# RH005_1.net
KiCad netlist of a schematic drawn in EAGLE
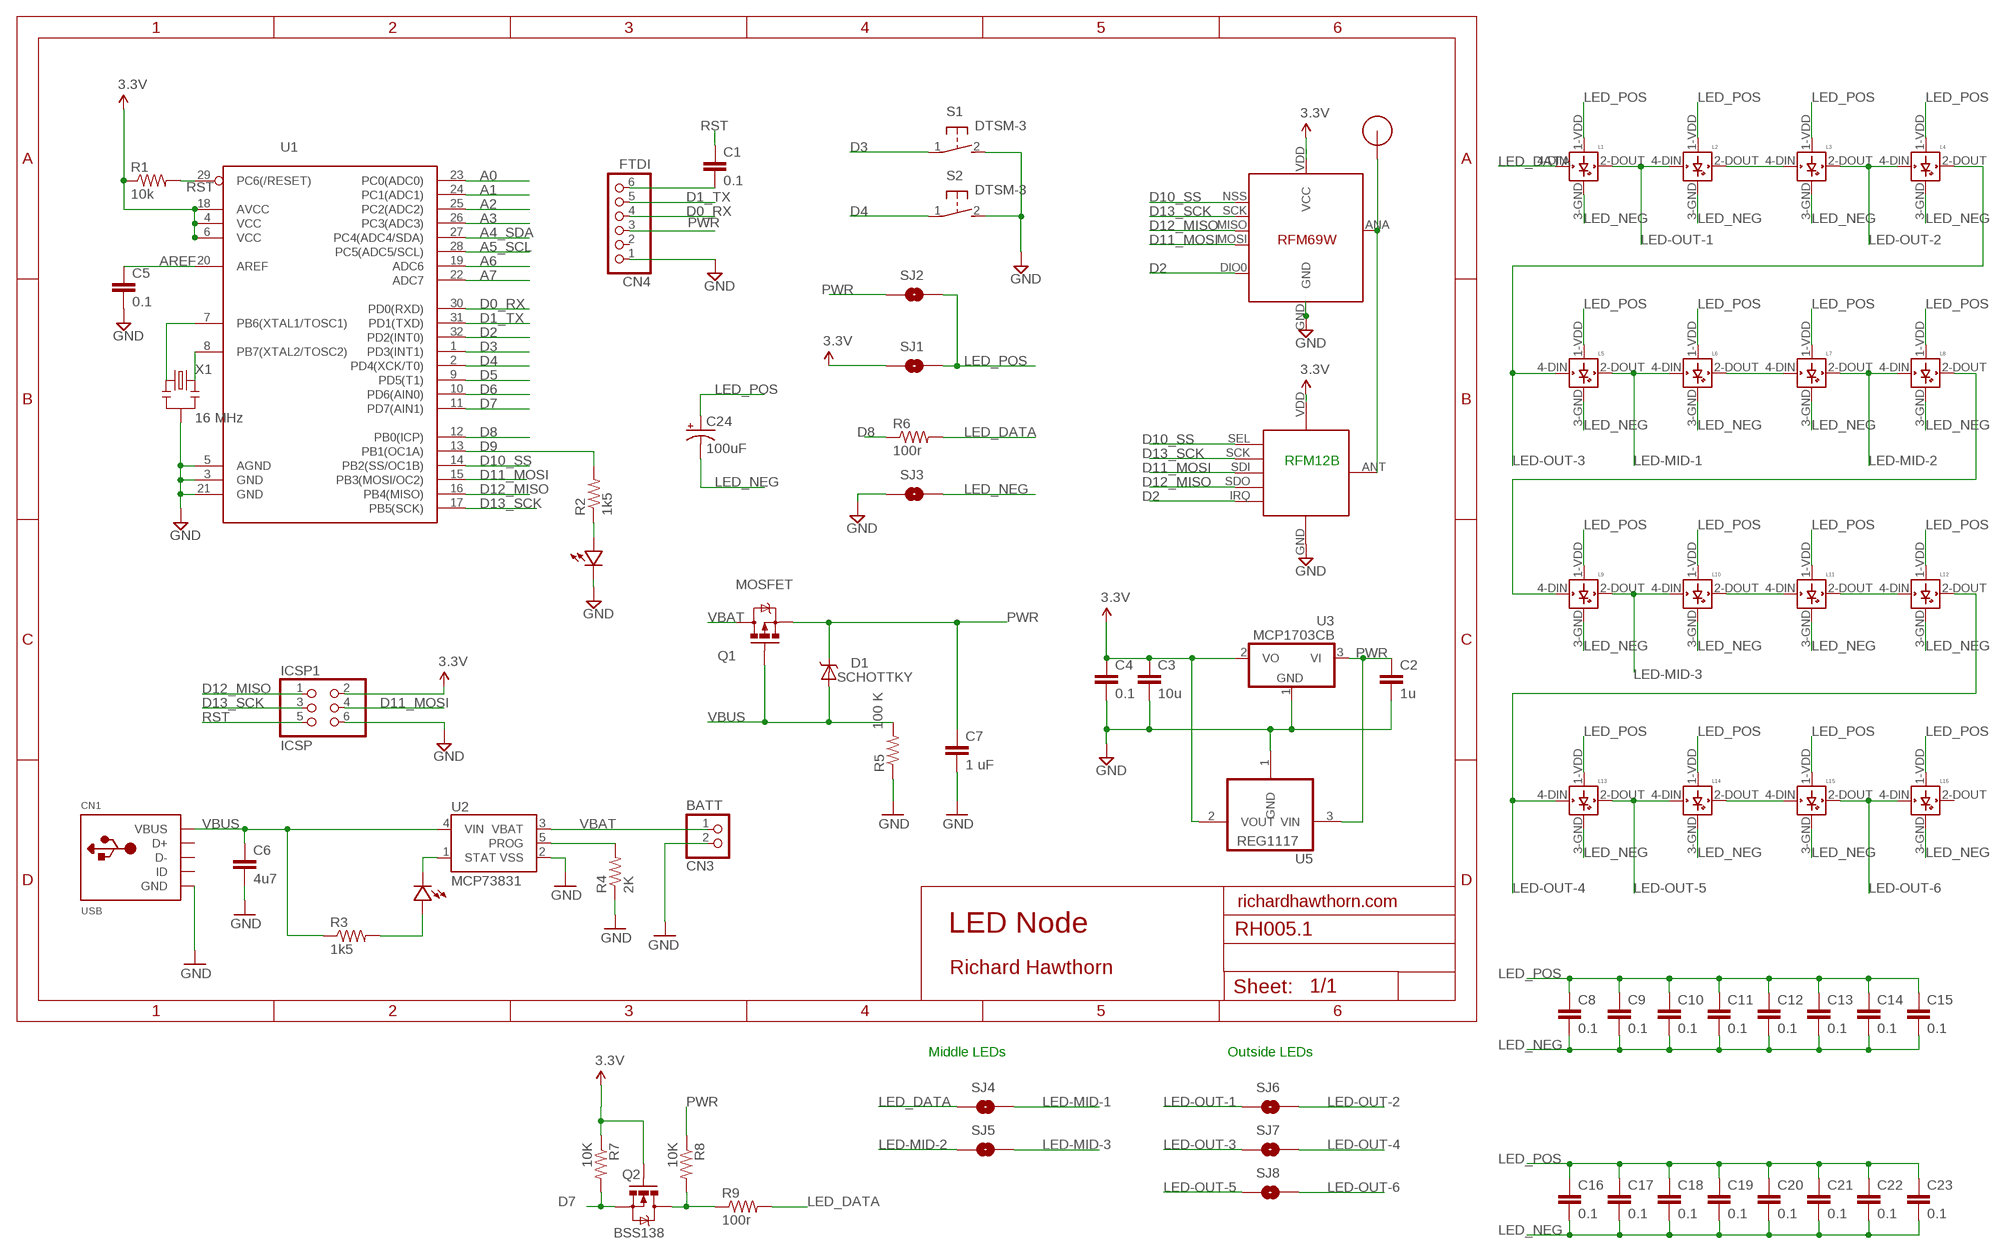
[diagram p0: schematic, sheet 1]

(export (version "E")
  (design (tool "Eeschema 10.0.6"))
  (components
    (comp (ref "C1")
      (value "0.1")
      (footprint "eagle-import:0603-CAP")
      (libsource (lib "eagle-import") (part "CAP0603-CAP"))
    )
    (comp (ref "C2")
      (value "1u")
      (footprint "eagle-import:0603-CAP")
      (libsource (lib "eagle-import") (part "CAP0603-CAP"))
    )
    (comp (ref "C3")
      (value "10u")
      (footprint "eagle-import:0805-CAP")
      (libsource (lib "eagle-import") (part "CAP0805-CAP"))
    )
    (comp (ref "C4")
      (value "0.1")
      (footprint "eagle-import:0603-CAP")
      (libsource (lib "eagle-import") (part "CAP0603-CAP"))
    )
    (comp (ref "C5")
      (value "0.1")
      (footprint "eagle-import:0603-CAP")
      (libsource (lib "eagle-import") (part "CAP0603-CAP"))
    )
    (comp (ref "C6")
      (value "4u7")
      (footprint "eagle-import:0603-CAP")
      (libsource (lib "eagle-import") (part "SparkFun_CAP0603-CAP"))
    )
    (comp (ref "C7")
      (value "1 uF")
      (footprint "eagle-import:0805")
      (libsource (lib "eagle-import") (part "SparkFun-Capacitors_CAP0805"))
    )
    (comp (ref "C8")
      (value "0.1")
      (footprint "eagle-import:0603-CAP")
      (libsource (lib "eagle-import") (part "CAP0603-CAP"))
    )
    (comp (ref "C9")
      (value "0.1")
      (footprint "eagle-import:0603-CAP")
      (libsource (lib "eagle-import") (part "CAP0603-CAP"))
    )
    (comp (ref "C10")
      (value "0.1")
      (footprint "eagle-import:0603-CAP")
      (libsource (lib "eagle-import") (part "CAP0603-CAP"))
    )
    (comp (ref "C11")
      (value "0.1")
      (footprint "eagle-import:0603-CAP")
      (libsource (lib "eagle-import") (part "CAP0603-CAP"))
    )
    (comp (ref "C12")
      (value "0.1")
      (footprint "eagle-import:0603-CAP")
      (libsource (lib "eagle-import") (part "CAP0603-CAP"))
    )
    (comp (ref "C13")
      (value "0.1")
      (footprint "eagle-import:0603-CAP")
      (libsource (lib "eagle-import") (part "CAP0603-CAP"))
    )
    (comp (ref "C14")
      (value "0.1")
      (footprint "eagle-import:0603-CAP")
      (libsource (lib "eagle-import") (part "CAP0603-CAP"))
    )
    (comp (ref "C15")
      (value "0.1")
      (footprint "eagle-import:0603-CAP")
      (libsource (lib "eagle-import") (part "CAP0603-CAP"))
    )
    (comp (ref "C16")
      (value "0.1")
      (footprint "eagle-import:0603-CAP")
      (libsource (lib "eagle-import") (part "CAP0603-CAP"))
    )
    (comp (ref "C17")
      (value "0.1")
      (footprint "eagle-import:0603-CAP")
      (libsource (lib "eagle-import") (part "CAP0603-CAP"))
    )
    (comp (ref "C18")
      (value "0.1")
      (footprint "eagle-import:0603-CAP")
      (libsource (lib "eagle-import") (part "CAP0603-CAP"))
    )
    (comp (ref "C19")
      (value "0.1")
      (footprint "eagle-import:0603-CAP")
      (libsource (lib "eagle-import") (part "CAP0603-CAP"))
    )
    (comp (ref "C20")
      (value "0.1")
      (footprint "eagle-import:0603-CAP")
      (libsource (lib "eagle-import") (part "CAP0603-CAP"))
    )
    (comp (ref "C21")
      (value "0.1")
      (footprint "eagle-import:0603-CAP")
      (libsource (lib "eagle-import") (part "CAP0603-CAP"))
    )
    (comp (ref "C22")
      (value "0.1")
      (footprint "eagle-import:0603-CAP")
      (libsource (lib "eagle-import") (part "CAP0603-CAP"))
    )
    (comp (ref "C23")
      (value "0.1")
      (footprint "eagle-import:0603-CAP")
      (libsource (lib "eagle-import") (part "CAP0603-CAP"))
    )
    (comp (ref "C24")
      (value "100uF")
      (footprint "eagle-import:EIA7343")
      (libsource (lib "eagle-import") (part "100UF-10V-10%(TANT)"))
    )
    (comp (ref "CN1")
      (value "USB")
      (footprint "eagle-import:USB-MINIB")
      (libsource (lib "eagle-import") (part "USBMINIB"))
    )
    (comp (ref "CN3")
      (value "BATT")
      (footprint "eagle-import:JST-PH-2-SMT-RA")
      (libsource (lib "eagle-import") (part "JST_2PIN-SMT-RA"))
    )
    (comp (ref "CN4")
      (value "FTDI")
      (footprint "eagle-import:1X06")
      (libsource (lib "eagle-import") (part "PINHD-1X6"))
    )
    (comp (ref "D1")
      (value "SCHOTTKY")
      (footprint "eagle-import:SMA-DIODE")
      (libsource (lib "eagle-import") (part "DIODE-SCHOTTKY_"))
    )
    (comp (ref "ICSP1")
      (value "ICSP")
      (footprint "eagle-import:2X03")
      (libsource (lib "eagle-import") (part "PINHD-2X3"))
    )
    (comp (ref "L1")
      (value "WS2812B")
      (footprint "eagle-import:WS2812B")
      (libsource (lib "eagle-import") (part "WS2812B"))
    )
    (comp (ref "L2")
      (value "WS2812B")
      (footprint "eagle-import:WS2812B")
      (libsource (lib "eagle-import") (part "WS2812B"))
    )
    (comp (ref "L3")
      (value "WS2812B")
      (footprint "eagle-import:WS2812B")
      (libsource (lib "eagle-import") (part "WS2812B"))
    )
    (comp (ref "L4")
      (value "WS2812B")
      (footprint "eagle-import:WS2812B")
      (libsource (lib "eagle-import") (part "WS2812B"))
    )
    (comp (ref "L5")
      (value "WS2812B")
      (footprint "eagle-import:WS2812B")
      (libsource (lib "eagle-import") (part "WS2812B"))
    )
    (comp (ref "L6")
      (value "WS2812B")
      (footprint "eagle-import:WS2812B")
      (libsource (lib "eagle-import") (part "WS2812B"))
    )
    (comp (ref "L7")
      (value "WS2812B")
      (footprint "eagle-import:WS2812B")
      (libsource (lib "eagle-import") (part "WS2812B"))
    )
    (comp (ref "L8")
      (value "WS2812B")
      (footprint "eagle-import:WS2812B")
      (libsource (lib "eagle-import") (part "WS2812B"))
    )
    (comp (ref "L9")
      (value "WS2812B")
      (footprint "eagle-import:WS2812B")
      (libsource (lib "eagle-import") (part "WS2812B"))
    )
    (comp (ref "L10")
      (value "WS2812B")
      (footprint "eagle-import:WS2812B")
      (libsource (lib "eagle-import") (part "WS2812B"))
    )
    (comp (ref "L11")
      (value "WS2812B")
      (footprint "eagle-import:WS2812B")
      (libsource (lib "eagle-import") (part "WS2812B"))
    )
    (comp (ref "L12")
      (value "WS2812B")
      (footprint "eagle-import:WS2812B")
      (libsource (lib "eagle-import") (part "WS2812B"))
    )
    (comp (ref "L13")
      (value "WS2812B")
      (footprint "eagle-import:WS2812B")
      (libsource (lib "eagle-import") (part "WS2812B"))
    )
    (comp (ref "L14")
      (value "WS2812B")
      (footprint "eagle-import:WS2812B")
      (libsource (lib "eagle-import") (part "WS2812B"))
    )
    (comp (ref "L15")
      (value "WS2812B")
      (footprint "eagle-import:WS2812B")
      (libsource (lib "eagle-import") (part "WS2812B"))
    )
    (comp (ref "L16")
      (value "WS2812B")
      (footprint "eagle-import:WS2812B")
      (libsource (lib "eagle-import") (part "WS2812B"))
    )
    (comp (ref "LED1")
      (value "LED0603")
      (footprint "eagle-import:0603-LED")
      (libsource (lib "eagle-import") (part "LED0603"))
    )
    (comp (ref "LED2")
      (value "LED0603")
      (footprint "eagle-import:0603-LED")
      (libsource (lib "eagle-import") (part "LED0603"))
    )
    (comp (ref "Q1")
      (value "MOSFET")
      (footprint "eagle-import:SOT23-3")
      (libsource (lib "eagle-import") (part "MOSFET-PCHANNELSMD"))
    )
    (comp (ref "Q2")
      (value "BSS138")
      (footprint "eagle-import:SOT23-3")
      (libsource (lib "eagle-import") (part "MOSFET-NCHANNELSMD"))
    )
    (comp (ref "R1")
      (value "10k")
      (footprint "eagle-import:0603-RES")
      (libsource (lib "eagle-import") (part "RESISTOR0603-RES"))
    )
    (comp (ref "R2")
      (value "1k5")
      (footprint "eagle-import:0603-RES")
      (libsource (lib "eagle-import") (part "RESISTOR0603-RES"))
    )
    (comp (ref "R3")
      (value "1k5")
      (footprint "eagle-import:0603-RES")
      (libsource (lib "eagle-import") (part "RESISTOR0603-RES"))
    )
    (comp (ref "R4")
      (value "2K")
      (footprint "eagle-import:0603-RES")
      (libsource (lib "eagle-import") (part "RESISTOR0603-RES"))
    )
    (comp (ref "R5")
      (value "100 K")
      (footprint "eagle-import:0805")
      (libsource (lib "eagle-import") (part "SparkFun-Resistors_RESISTOR0805-RES"))
    )
    (comp (ref "R6")
      (value "100r")
      (footprint "eagle-import:0603-RES")
      (libsource (lib "eagle-import") (part "RESISTOR0603-RES"))
    )
    (comp (ref "R7")
      (value "10K")
      (footprint "eagle-import:0805")
      (libsource (lib "eagle-import") (part "SparkFun-Passives_RESISTOR0805-RES"))
    )
    (comp (ref "R8")
      (value "10K")
      (footprint "eagle-import:0805")
      (libsource (lib "eagle-import") (part "SparkFun-Passives_RESISTOR0805-RES"))
    )
    (comp (ref "R9")
      (value "100r")
      (footprint "eagle-import:0603-RES")
      (libsource (lib "eagle-import") (part "RESISTOR0603-RES"))
    )
    (comp (ref "RF1")
      (value "RFM12B")
      (footprint "eagle-import:RFM12B-MINPADS")
      (libsource (lib "eagle-import") (part "RFM12B_MINPADS"))
    )
    (comp (ref "RF2")
      (value "RFM69")
      (footprint "eagle-import:RFM69W-MINPADS")
      (libsource (lib "eagle-import") (part "RFM69"))
    )
    (comp (ref "S1")
      (value "DTSM-3")
      (footprint "eagle-import:DTSM-3")
      (libsource (lib "eagle-import") (part "DTSM-3"))
    )
    (comp (ref "S2")
      (value "DTSM-3")
      (footprint "eagle-import:DTSM-3")
      (libsource (lib "eagle-import") (part "DTSM-3"))
    )
    (comp (ref "SJ1")
      (value "SOLDERJUMPERNO")
      (footprint "eagle-import:SJ_2S-NO")
      (libsource (lib "eagle-import") (part "SOLDERJUMPERNO"))
    )
    (comp (ref "SJ2")
      (value "SOLDERJUMPERNO")
      (footprint "eagle-import:SJ_2S-NO")
      (libsource (lib "eagle-import") (part "SOLDERJUMPERNO"))
    )
    (comp (ref "SJ3")
      (value "SOLDERJUMPERNO")
      (footprint "eagle-import:SJ_2S-NO")
      (libsource (lib "eagle-import") (part "SOLDERJUMPERNO"))
    )
    (comp (ref "SJ4")
      (value "JUMPER-PAD-2-NOYES_SILK")
      (footprint "eagle-import:PAD-JUMPER-2-NO_YES_SILK")
      (libsource (lib "eagle-import") (part "JUMPER-PAD-2-NOYES_SILK"))
    )
    (comp (ref "SJ5")
      (value "JUMPER-PAD-2-NOYES_SILK")
      (footprint "eagle-import:PAD-JUMPER-2-NO_YES_SILK")
      (libsource (lib "eagle-import") (part "JUMPER-PAD-2-NOYES_SILK"))
    )
    (comp (ref "SJ6")
      (value "JUMPER-PAD-2-NOYES_SILK")
      (footprint "eagle-import:PAD-JUMPER-2-NO_YES_SILK")
      (libsource (lib "eagle-import") (part "JUMPER-PAD-2-NOYES_SILK"))
    )
    (comp (ref "SJ7")
      (value "JUMPER-PAD-2-NOYES_SILK")
      (footprint "eagle-import:PAD-JUMPER-2-NO_YES_SILK")
      (libsource (lib "eagle-import") (part "JUMPER-PAD-2-NOYES_SILK"))
    )
    (comp (ref "SJ8")
      (value "JUMPER-PAD-2-NOYES_SILK")
      (footprint "eagle-import:PAD-JUMPER-2-NO_YES_SILK")
      (libsource (lib "eagle-import") (part "JUMPER-PAD-2-NOYES_SILK"))
    )
    (comp (ref "U$1")
      (value "RFM12B_ANTENNA")
      (footprint "eagle-import:RFM12B-ANTENNA")
      (libsource (lib "eagle-import") (part "RFM12B_ANTENNA"))
    )
    (comp (ref "U1")
      (value "ATMega-328")
      (footprint "eagle-import:TQFP32-08")
      (libsource (lib "eagle-import") (part "ATMEGA168/328TQFP32"))
    )
    (comp (ref "U2")
      (value "MCP73831")
      (footprint "eagle-import:SOT23-5")
      (libsource (lib "eagle-import") (part "MCP73831"))
    )
    (comp (ref "U3")
      (value "MCP1703CB")
      (footprint "eagle-import:SOT23")
      (libsource (lib "eagle-import") (part "MCP1703CB"))
    )
    (comp (ref "U5")
      (value "REG1117")
      (footprint "eagle-import:SOT223")
      (libsource (lib "eagle-import") (part "REG1117"))
    )
    (comp (ref "X1")
      (value "16 MHz")
      (footprint "eagle-import:RESONATOR-SMD")
      (libsource (lib "eagle-import") (part "RESONATORSMD"))
    )
  )
  (nets
    (net (code "1") (name "/A0") (class "Default")
      (node (ref "U1") (pin "23") (pinfunction "PC0(ADC0)_23") (pintype "bidirectional"))
    )
    (net (code "2") (name "/A1") (class "Default")
      (node (ref "U1") (pin "24") (pinfunction "PC1(ADC1)_24") (pintype "bidirectional"))
    )
    (net (code "3") (name "/A2") (class "Default")
      (node (ref "U1") (pin "25") (pinfunction "PC2(ADC2)_25") (pintype "bidirectional"))
    )
    (net (code "4") (name "/A3") (class "Default")
      (node (ref "U1") (pin "26") (pinfunction "PC3(ADC3)_26") (pintype "bidirectional"))
    )
    (net (code "5") (name "/A4_SDA") (class "Default")
      (node (ref "U1") (pin "27") (pinfunction "PC4(ADC4/SDA)_27") (pintype "bidirectional"))
    )
    (net (code "6") (name "/A5_SCL") (class "Default")
      (node (ref "U1") (pin "28") (pinfunction "PC5(ADC5/SCL)_28") (pintype "bidirectional"))
    )
    (net (code "7") (name "/A6") (class "Default")
      (node (ref "U1") (pin "19") (pinfunction "ADC6_19") (pintype "bidirectional"))
    )
    (net (code "8") (name "/A7") (class "Default")
      (node (ref "U1") (pin "22") (pinfunction "ADC7_22") (pintype "bidirectional"))
    )
    (net (code "9") (name "/AREF") (class "Default")
      (node (ref "C5") (pin "1") (pinfunction "1_1") (pintype "passive"))
      (node (ref "U1") (pin "20") (pinfunction "AREF_20") (pintype "bidirectional"))
    )
    (net (code "10") (name "/D0_RX") (class "Default")
      (node (ref "CN4") (pin "4") (pinfunction "4_4") (pintype "passive"))
      (node (ref "U1") (pin "30") (pinfunction "PD0(RXD)_30") (pintype "bidirectional"))
    )
    (net (code "11") (name "/D1_TX") (class "Default")
      (node (ref "CN4") (pin "5") (pinfunction "5_5") (pintype "passive"))
      (node (ref "U1") (pin "31") (pinfunction "PD1(TXD)_31") (pintype "bidirectional"))
    )
    (net (code "12") (name "/D2") (class "Default")
      (node (ref "RF1") (pin "IRQ") (pinfunction "IRQ_IRQ") (pintype "bidirectional"))
      (node (ref "RF2") (pin "DIO0") (pinfunction "DIO0_DIO0") (pintype "open_collector"))
      (node (ref "U1") (pin "32") (pinfunction "PD2(INT0)_32") (pintype "bidirectional"))
    )
    (net (code "13") (name "/D3") (class "Default")
      (node (ref "S1") (pin "1") (pinfunction "1_1") (pintype "passive"))
      (node (ref "U1") (pin "1") (pinfunction "PD3(INT1)_1") (pintype "bidirectional"))
    )
    (net (code "14") (name "/D4") (class "Default")
      (node (ref "S2") (pin "1") (pinfunction "1_1") (pintype "passive"))
      (node (ref "U1") (pin "2") (pinfunction "PD4(XCK/T0)_2") (pintype "bidirectional"))
    )
    (net (code "15") (name "/D5") (class "Default")
      (node (ref "U1") (pin "9") (pinfunction "PD5(T1)_9") (pintype "bidirectional"))
    )
    (net (code "16") (name "/D6") (class "Default")
      (node (ref "U1") (pin "10") (pinfunction "PD6(AIN0)_10") (pintype "bidirectional"))
    )
    (net (code "17") (name "/D7") (class "Default")
      (node (ref "Q2") (pin "2") (pinfunction "S_2") (pintype "passive"))
      (node (ref "R7") (pin "2") (pinfunction "2_2") (pintype "passive"))
      (node (ref "U1") (pin "11") (pinfunction "PD7(AIN1)_11") (pintype "bidirectional"))
    )
    (net (code "18") (name "/D8") (class "Default")
      (node (ref "R6") (pin "1") (pinfunction "1_1") (pintype "passive"))
      (node (ref "U1") (pin "12") (pinfunction "PB0(ICP)_12") (pintype "bidirectional"))
    )
    (net (code "19") (name "/D9") (class "Default")
      (node (ref "R2") (pin "2") (pinfunction "2_2") (pintype "passive"))
      (node (ref "U1") (pin "13") (pinfunction "PB1(OC1A)_13") (pintype "bidirectional"))
    )
    (net (code "20") (name "/D10_SS") (class "Default")
      (node (ref "RF1") (pin "SEL") (pinfunction "SEL_SEL") (pintype "bidirectional"))
      (node (ref "RF2") (pin "NSS") (pinfunction "SEL_NSS") (pintype "input"))
      (node (ref "U1") (pin "14") (pinfunction "PB2(SS/OC1B)_14") (pintype "bidirectional"))
    )
    (net (code "21") (name "/D11_MOSI") (class "Default")
      (node (ref "ICSP1") (pin "4") (pinfunction "4_4") (pintype "passive"))
      (node (ref "RF1") (pin "SDI") (pinfunction "SDI/MOSI_SDI") (pintype "bidirectional"))
      (node (ref "RF2") (pin "MOSI") (pinfunction "MOSI_MOSI") (pintype "output"))
      (node (ref "U1") (pin "15") (pinfunction "PB3(MOSI/OC2)_15") (pintype "bidirectional"))
    )
    (net (code "22") (name "/D12_MISO") (class "Default")
      (node (ref "ICSP1") (pin "1") (pinfunction "1_1") (pintype "passive"))
      (node (ref "RF1") (pin "SDO") (pinfunction "SDO/MISO_SDO") (pintype "bidirectional"))
      (node (ref "RF2") (pin "MISO") (pinfunction "MISO_MISO") (pintype "input"))
      (node (ref "U1") (pin "16") (pinfunction "PB4(MISO)_16") (pintype "bidirectional"))
    )
    (net (code "23") (name "/D13_SCK") (class "Default")
      (node (ref "ICSP1") (pin "3") (pinfunction "3_3") (pintype "passive"))
      (node (ref "RF1") (pin "SCK") (pinfunction "SCK_SCK") (pintype "bidirectional"))
      (node (ref "RF2") (pin "SCK") (pinfunction "SCK_SCK") (pintype "input"))
      (node (ref "U1") (pin "17") (pinfunction "PB5(SCK)_17") (pintype "bidirectional"))
    )
    (net (code "24") (name "/LED-MID-1") (class "Default")
      (node (ref "L5") (pin "2-DOUT") (pinfunction "DOUT_2-DOUT") (pintype "output"))
      (node (ref "L6") (pin "4-DIN") (pinfunction "DIN_4-DIN") (pintype "input"))
      (node (ref "SJ4") (pin "2") (pinfunction "2_2") (pintype "passive"))
    )
    (net (code "25") (name "/LED-MID-2") (class "Default")
      (node (ref "L7") (pin "2-DOUT") (pinfunction "DOUT_2-DOUT") (pintype "output"))
      (node (ref "L8") (pin "4-DIN") (pinfunction "DIN_4-DIN") (pintype "input"))
      (node (ref "SJ5") (pin "1") (pinfunction "1_1") (pintype "passive"))
    )
    (net (code "26") (name "/LED-MID-3") (class "Default")
      (node (ref "L10") (pin "4-DIN") (pinfunction "DIN_4-DIN") (pintype "input"))
      (node (ref "L9") (pin "2-DOUT") (pinfunction "DOUT_2-DOUT") (pintype "output"))
      (node (ref "SJ5") (pin "2") (pinfunction "2_2") (pintype "passive"))
    )
    (net (code "27") (name "/LED-OUT-1") (class "Default")
      (node (ref "L1") (pin "2-DOUT") (pinfunction "DOUT_2-DOUT") (pintype "output"))
      (node (ref "L2") (pin "4-DIN") (pinfunction "DIN_4-DIN") (pintype "input"))
      (node (ref "SJ6") (pin "1") (pinfunction "1_1") (pintype "passive"))
    )
    (net (code "28") (name "/LED-OUT-2") (class "Default")
      (node (ref "L3") (pin "2-DOUT") (pinfunction "DOUT_2-DOUT") (pintype "output"))
      (node (ref "L4") (pin "4-DIN") (pinfunction "DIN_4-DIN") (pintype "input"))
      (node (ref "SJ6") (pin "2") (pinfunction "2_2") (pintype "passive"))
    )
    (net (code "29") (name "/LED-OUT-3") (class "Default")
      (node (ref "L4") (pin "2-DOUT") (pinfunction "DOUT_2-DOUT") (pintype "output"))
      (node (ref "L5") (pin "4-DIN") (pinfunction "DIN_4-DIN") (pintype "input"))
      (node (ref "SJ7") (pin "1") (pinfunction "1_1") (pintype "passive"))
    )
    (net (code "30") (name "/LED-OUT-4") (class "Default")
      (node (ref "L12") (pin "2-DOUT") (pinfunction "DOUT_2-DOUT") (pintype "output"))
      (node (ref "L13") (pin "4-DIN") (pinfunction "DIN_4-DIN") (pintype "input"))
      (node (ref "SJ7") (pin "2") (pinfunction "2_2") (pintype "passive"))
    )
    (net (code "31") (name "/LED-OUT-5") (class "Default")
      (node (ref "L13") (pin "2-DOUT") (pinfunction "DOUT_2-DOUT") (pintype "output"))
      (node (ref "L14") (pin "4-DIN") (pinfunction "DIN_4-DIN") (pintype "input"))
      (node (ref "SJ8") (pin "1") (pinfunction "1_1") (pintype "passive"))
    )
    (net (code "32") (name "/LED-OUT-6") (class "Default")
      (node (ref "L15") (pin "2-DOUT") (pinfunction "DOUT_2-DOUT") (pintype "output"))
      (node (ref "L16") (pin "4-DIN") (pinfunction "DIN_4-DIN") (pintype "input"))
      (node (ref "SJ8") (pin "2") (pinfunction "2_2") (pintype "passive"))
    )
    (net (code "33") (name "/LED_DATA") (class "Default")
      (node (ref "L1") (pin "4-DIN") (pinfunction "DIN_4-DIN") (pintype "input"))
      (node (ref "R6") (pin "2") (pinfunction "2_2") (pintype "passive"))
      (node (ref "R9") (pin "2") (pinfunction "2_2") (pintype "passive"))
      (node (ref "SJ4") (pin "1") (pinfunction "1_1") (pintype "passive"))
    )
    (net (code "34") (name "/LED_NEG") (class "Default")
      (node (ref "C10") (pin "2") (pinfunction "2_2") (pintype "passive"))
      (node (ref "C11") (pin "2") (pinfunction "2_2") (pintype "passive"))
      (node (ref "C12") (pin "2") (pinfunction "2_2") (pintype "passive"))
      (node (ref "C13") (pin "2") (pinfunction "2_2") (pintype "passive"))
      (node (ref "C14") (pin "2") (pinfunction "2_2") (pintype "passive"))
      (node (ref "C15") (pin "2") (pinfunction "2_2") (pintype "passive"))
      (node (ref "C16") (pin "2") (pinfunction "2_2") (pintype "passive"))
      (node (ref "C17") (pin "2") (pinfunction "2_2") (pintype "passive"))
      (node (ref "C18") (pin "2") (pinfunction "2_2") (pintype "passive"))
      (node (ref "C19") (pin "2") (pinfunction "2_2") (pintype "passive"))
      (node (ref "C20") (pin "2") (pinfunction "2_2") (pintype "passive"))
      (node (ref "C21") (pin "2") (pinfunction "2_2") (pintype "passive"))
      (node (ref "C22") (pin "2") (pinfunction "2_2") (pintype "passive"))
      (node (ref "C23") (pin "2") (pinfunction "2_2") (pintype "passive"))
      (node (ref "C24") (pin "C") (pinfunction "-_C") (pintype "passive"))
      (node (ref "C8") (pin "2") (pinfunction "2_2") (pintype "passive"))
      (node (ref "C9") (pin "2") (pinfunction "2_2") (pintype "passive"))
      (node (ref "L1") (pin "3-GND") (pinfunction "GND_3-GND") (pintype "bidirectional"))
      (node (ref "L10") (pin "3-GND") (pinfunction "GND_3-GND") (pintype "bidirectional"))
      (node (ref "L11") (pin "3-GND") (pinfunction "GND_3-GND") (pintype "bidirectional"))
      (node (ref "L12") (pin "3-GND") (pinfunction "GND_3-GND") (pintype "bidirectional"))
      (node (ref "L13") (pin "3-GND") (pinfunction "GND_3-GND") (pintype "bidirectional"))
      (node (ref "L14") (pin "3-GND") (pinfunction "GND_3-GND") (pintype "bidirectional"))
      (node (ref "L15") (pin "3-GND") (pinfunction "GND_3-GND") (pintype "bidirectional"))
      (node (ref "L16") (pin "3-GND") (pinfunction "GND_3-GND") (pintype "bidirectional"))
      (node (ref "L2") (pin "3-GND") (pinfunction "GND_3-GND") (pintype "bidirectional"))
      (node (ref "L3") (pin "3-GND") (pinfunction "GND_3-GND") (pintype "bidirectional"))
      (node (ref "L4") (pin "3-GND") (pinfunction "GND_3-GND") (pintype "bidirectional"))
      (node (ref "L5") (pin "3-GND") (pinfunction "GND_3-GND") (pintype "bidirectional"))
      (node (ref "L6") (pin "3-GND") (pinfunction "GND_3-GND") (pintype "bidirectional"))
      (node (ref "L7") (pin "3-GND") (pinfunction "GND_3-GND") (pintype "bidirectional"))
      (node (ref "L8") (pin "3-GND") (pinfunction "GND_3-GND") (pintype "bidirectional"))
      (node (ref "L9") (pin "3-GND") (pinfunction "GND_3-GND") (pintype "bidirectional"))
      (node (ref "SJ3") (pin "2") (pinfunction "2_2") (pintype "passive"))
    )
    (net (code "35") (name "/LED_POS") (class "Default")
      (node (ref "C10") (pin "1") (pinfunction "1_1") (pintype "passive"))
      (node (ref "C11") (pin "1") (pinfunction "1_1") (pintype "passive"))
      (node (ref "C12") (pin "1") (pinfunction "1_1") (pintype "passive"))
      (node (ref "C13") (pin "1") (pinfunction "1_1") (pintype "passive"))
      (node (ref "C14") (pin "1") (pinfunction "1_1") (pintype "passive"))
      (node (ref "C15") (pin "1") (pinfunction "1_1") (pintype "passive"))
      (node (ref "C16") (pin "1") (pinfunction "1_1") (pintype "passive"))
      (node (ref "C17") (pin "1") (pinfunction "1_1") (pintype "passive"))
      (node (ref "C18") (pin "1") (pinfunction "1_1") (pintype "passive"))
      (node (ref "C19") (pin "1") (pinfunction "1_1") (pintype "passive"))
      (node (ref "C20") (pin "1") (pinfunction "1_1") (pintype "passive"))
      (node (ref "C21") (pin "1") (pinfunction "1_1") (pintype "passive"))
      (node (ref "C22") (pin "1") (pinfunction "1_1") (pintype "passive"))
      (node (ref "C23") (pin "1") (pinfunction "1_1") (pintype "passive"))
      (node (ref "C24") (pin "A") (pinfunction "+_A") (pintype "passive"))
      (node (ref "C8") (pin "1") (pinfunction "1_1") (pintype "passive"))
      (node (ref "C9") (pin "1") (pinfunction "1_1") (pintype "passive"))
      (node (ref "L1") (pin "1-VDD") (pinfunction "VDD_1-VDD") (pintype "bidirectional"))
      (node (ref "L10") (pin "1-VDD") (pinfunction "VDD_1-VDD") (pintype "bidirectional"))
      (node (ref "L11") (pin "1-VDD") (pinfunction "VDD_1-VDD") (pintype "bidirectional"))
      (node (ref "L12") (pin "1-VDD") (pinfunction "VDD_1-VDD") (pintype "bidirectional"))
      (node (ref "L13") (pin "1-VDD") (pinfunction "VDD_1-VDD") (pintype "bidirectional"))
      (node (ref "L14") (pin "1-VDD") (pinfunction "VDD_1-VDD") (pintype "bidirectional"))
      (node (ref "L15") (pin "1-VDD") (pinfunction "VDD_1-VDD") (pintype "bidirectional"))
      (node (ref "L16") (pin "1-VDD") (pinfunction "VDD_1-VDD") (pintype "bidirectional"))
      (node (ref "L2") (pin "1-VDD") (pinfunction "VDD_1-VDD") (pintype "bidirectional"))
      (node (ref "L3") (pin "1-VDD") (pinfunction "VDD_1-VDD") (pintype "bidirectional"))
      (node (ref "L4") (pin "1-VDD") (pinfunction "VDD_1-VDD") (pintype "bidirectional"))
      (node (ref "L5") (pin "1-VDD") (pinfunction "VDD_1-VDD") (pintype "bidirectional"))
      (node (ref "L6") (pin "1-VDD") (pinfunction "VDD_1-VDD") (pintype "bidirectional"))
      (node (ref "L7") (pin "1-VDD") (pinfunction "VDD_1-VDD") (pintype "bidirectional"))
      (node (ref "L8") (pin "1-VDD") (pinfunction "VDD_1-VDD") (pintype "bidirectional"))
      (node (ref "L9") (pin "1-VDD") (pinfunction "VDD_1-VDD") (pintype "bidirectional"))
      (node (ref "SJ1") (pin "2") (pinfunction "2_2") (pintype "passive"))
      (node (ref "SJ2") (pin "2") (pinfunction "2_2") (pintype "passive"))
    )
    (net (code "36") (name "/PWR") (class "Default")
      (node (ref "C2") (pin "1") (pinfunction "1_1") (pintype "passive"))
      (node (ref "C7") (pin "1") (pinfunction "1_1") (pintype "passive"))
      (node (ref "CN4") (pin "3") (pinfunction "3_3") (pintype "passive"))
      (node (ref "D1") (pin "C") (pinfunction "C_C") (pintype "passive"))
      (node (ref "Q1") (pin "2") (pinfunction "S_2") (pintype "passive"))
      (node (ref "R8") (pin "1") (pinfunction "1_1") (pintype "passive"))
      (node (ref "SJ2") (pin "1") (pinfunction "1_1") (pintype "passive"))
      (node (ref "U3") (pin "3") (pinfunction "VI_3") (pintype "input"))
      (node (ref "U5") (pin "3") (pinfunction "VIN_3") (pintype "input"))
    )
    (net (code "37") (name "/RST") (class "Default")
      (node (ref "C1") (pin "1") (pinfunction "1_1") (pintype "passive"))
      (node (ref "ICSP1") (pin "5") (pinfunction "5_5") (pintype "passive"))
      (node (ref "R1") (pin "2") (pinfunction "2_2") (pintype "passive"))
      (node (ref "U1") (pin "29") (pinfunction "PC6(/RESET)_29") (pintype "bidirectional"))
    )
    (net (code "38") (name "/VBAT") (class "Default")
      (node (ref "CN3") (pin "1") (pinfunction "2_1") (pintype "passive"))
      (node (ref "Q1") (pin "3") (pinfunction "D_3") (pintype "passive"))
      (node (ref "U2") (pin "3") (pinfunction "VBAT_3") (pintype "power_in"))
    )
    (net (code "39") (name "/VBUS") (class "Default")
      (node (ref "C6") (pin "1") (pinfunction "1_1") (pintype "passive"))
      (node (ref "CN1") (pin "VBUS") (pinfunction "VBUS_VBUS") (pintype "power_in"))
      (node (ref "D1") (pin "A") (pinfunction "A_A") (pintype "passive"))
      (node (ref "Q1") (pin "1") (pinfunction "G_1") (pintype "passive"))
      (node (ref "R3") (pin "1") (pinfunction "1_1") (pintype "passive"))
      (node (ref "R5") (pin "2") (pinfunction "2_2") (pintype "passive"))
      (node (ref "U2") (pin "4") (pinfunction "VIN_4") (pintype "power_in"))
    )
    (net (code "40") (name "3.3V") (class "Default")
      (node (ref "C3") (pin "1") (pinfunction "1_1") (pintype "passive"))
      (node (ref "C4") (pin "1") (pinfunction "1_1") (pintype "passive"))
      (node (ref "ICSP1") (pin "2") (pinfunction "2_2") (pintype "passive"))
      (node (ref "Q2") (pin "1") (pinfunction "G_1") (pintype "passive"))
      (node (ref "R1") (pin "1") (pinfunction "1_1") (pintype "passive"))
      (node (ref "R7") (pin "1") (pinfunction "1_1") (pintype "passive"))
      (node (ref "RF1") (pin "VDD") (pinfunction "VDD_VDD") (pintype "bidirectional"))
      (node (ref "RF2") (pin "VDD") (pinfunction "VCC_VDD") (pintype "power_in"))
      (node (ref "SJ1") (pin "1") (pinfunction "1_1") (pintype "passive"))
      (node (ref "U1") (pin "18") (pinfunction "AVCC_18") (pintype "bidirectional"))
      (node (ref "U1") (pin "4") (pinfunction "VCC_4") (pintype "bidirectional"))
      (node (ref "U1") (pin "6") (pinfunction "VCC_6") (pintype "bidirectional"))
      (node (ref "U3") (pin "2") (pinfunction "VO_2") (pintype "passive"))
      (node (ref "U5") (pin "2") (pinfunction "VOUT_2") (pintype "output"))
    )
    (net (code "41") (name "GND") (class "Default")
      (node (ref "C2") (pin "2") (pinfunction "2_2") (pintype "passive"))
      (node (ref "C3") (pin "2") (pinfunction "2_2") (pintype "passive"))
      (node (ref "C4") (pin "2") (pinfunction "2_2") (pintype "passive"))
      (node (ref "C5") (pin "2") (pinfunction "2_2") (pintype "passive"))
      (node (ref "C6") (pin "2") (pinfunction "2_2") (pintype "passive"))
      (node (ref "C7") (pin "2") (pinfunction "2_2") (pintype "passive"))
      (node (ref "CN1") (pin "GND") (pinfunction "GND_GND") (pintype "power_in"))
      (node (ref "CN3") (pin "2") (pinfunction "1_2") (pintype "passive"))
      (node (ref "CN4") (pin "1") (pinfunction "1_1") (pintype "passive"))
      (node (ref "ICSP1") (pin "6") (pinfunction "6_6") (pintype "passive"))
      (node (ref "LED2") (pin "MINUS") (pinfunction "MINUS_MINUS") (pintype "passive"))
      (node (ref "R4") (pin "1") (pinfunction "1_1") (pintype "passive"))
      (node (ref "R5") (pin "1") (pinfunction "1_1") (pintype "passive"))
      (node (ref "RF1") (pin "GND") (pinfunction "GND_GND") (pintype "bidirectional"))
      (node (ref "RF2") (pin "GND") (pinfunction "GND_GND") (pintype "power_in"))
      (node (ref "S1") (pin "2") (pinfunction "2_2") (pintype "passive"))
      (node (ref "S2") (pin "2") (pinfunction "2_2") (pintype "passive"))
      (node (ref "SJ3") (pin "1") (pinfunction "1_1") (pintype "passive"))
      (node (ref "U1") (pin "21") (pinfunction "GND_21") (pintype "bidirectional"))
      (node (ref "U1") (pin "3") (pinfunction "GND_3") (pintype "bidirectional"))
      (node (ref "U1") (pin "5") (pinfunction "AGND_5") (pintype "bidirectional"))
      (node (ref "U2") (pin "2") (pinfunction "VSS_2") (pintype "power_in"))
      (node (ref "U3") (pin "1") (pinfunction "GND_1") (pintype "passive"))
      (node (ref "U5") (pin "1") (pinfunction "GND_1") (pintype "power_in"))
      (node (ref "X1") (pin "2") (pinfunction "2_2") (pintype "passive"))
    )
    (net (code "42") (name "Net-(C1-Pad2)") (class "Default")
      (node (ref "C1") (pin "2") (pinfunction "2_2") (pintype "passive"))
      (node (ref "CN4") (pin "6") (pinfunction "6_6") (pintype "passive"))
    )
    (net (code "43") (name "Net-(L2-DOUT)") (class "Default")
      (node (ref "L2") (pin "2-DOUT") (pinfunction "DOUT_2-DOUT") (pintype "output"))
      (node (ref "L3") (pin "4-DIN") (pinfunction "DIN_4-DIN") (pintype "input"))
    )
    (net (code "44") (name "Net-(L6-DOUT)") (class "Default")
      (node (ref "L6") (pin "2-DOUT") (pinfunction "DOUT_2-DOUT") (pintype "output"))
      (node (ref "L7") (pin "4-DIN") (pinfunction "DIN_4-DIN") (pintype "input"))
    )
    (net (code "45") (name "Net-(L8-DOUT)") (class "Default")
      (node (ref "L8") (pin "2-DOUT") (pinfunction "DOUT_2-DOUT") (pintype "output"))
      (node (ref "L9") (pin "4-DIN") (pinfunction "DIN_4-DIN") (pintype "input"))
    )
    (net (code "46") (name "Net-(L10-DOUT)") (class "Default")
      (node (ref "L10") (pin "2-DOUT") (pinfunction "DOUT_2-DOUT") (pintype "output"))
      (node (ref "L11") (pin "4-DIN") (pinfunction "DIN_4-DIN") (pintype "input"))
    )
    (net (code "47") (name "Net-(L11-DOUT)") (class "Default")
      (node (ref "L11") (pin "2-DOUT") (pinfunction "DOUT_2-DOUT") (pintype "output"))
      (node (ref "L12") (pin "4-DIN") (pinfunction "DIN_4-DIN") (pintype "input"))
    )
    (net (code "48") (name "Net-(L14-DOUT)") (class "Default")
      (node (ref "L14") (pin "2-DOUT") (pinfunction "DOUT_2-DOUT") (pintype "output"))
      (node (ref "L15") (pin "4-DIN") (pinfunction "DIN_4-DIN") (pintype "input"))
    )
    (net (code "49") (name "Net-(LED1-PadPLUS)") (class "Default")
      (node (ref "LED1") (pin "PLUS") (pinfunction "PLUS_PLUS") (pintype "passive"))
      (node (ref "R3") (pin "2") (pinfunction "2_2") (pintype "passive"))
    )
    (net (code "50") (name "Net-(LED2-PadPLUS)") (class "Default")
      (node (ref "LED2") (pin "PLUS") (pinfunction "PLUS_PLUS") (pintype "passive"))
      (node (ref "R2") (pin "1") (pinfunction "1_1") (pintype "passive"))
    )
    (net (code "51") (name "Net-(Q2-D)") (class "Default")
      (node (ref "Q2") (pin "3") (pinfunction "D_3") (pintype "passive"))
      (node (ref "R8") (pin "2") (pinfunction "2_2") (pintype "passive"))
      (node (ref "R9") (pin "1") (pinfunction "1_1") (pintype "passive"))
    )
    (net (code "52") (name "Net-(RF2-ANT)") (class "Default")
      (node (ref "RF1") (pin "ANT") (pinfunction "ANT_ANT") (pintype "bidirectional"))
      (node (ref "RF2") (pin "ANA") (pinfunction "ANT_ANA") (pintype "passive"))
      (node (ref "U$1") (pin "P$1") (pinfunction "1_P$1") (pintype "bidirectional"))
    )
    (net (code "53") (name "Net-(U1-PB6(XTAL1{slash}TOSC1))") (class "Default")
      (node (ref "U1") (pin "7") (pinfunction "PB6(XTAL1/TOSC1)_7") (pintype "bidirectional"))
      (node (ref "X1") (pin "1") (pinfunction "1_1") (pintype "passive"))
    )
    (net (code "54") (name "Net-(U1-PB7(XTAL2{slash}TOSC2))") (class "Default")
      (node (ref "U1") (pin "8") (pinfunction "PB7(XTAL2/TOSC2)_8") (pintype "bidirectional"))
      (node (ref "X1") (pin "3") (pinfunction "3_3") (pintype "passive"))
    )
    (net (code "55") (name "Net-(U2-PROG)") (class "Default")
      (node (ref "R4") (pin "2") (pinfunction "2_2") (pintype "passive"))
      (node (ref "U2") (pin "5") (pinfunction "PROG_5") (pintype "input"))
    )
    (net (code "56") (name "Net-(U2-STAT)") (class "Default")
      (node (ref "LED1") (pin "MINUS") (pinfunction "MINUS_MINUS") (pintype "passive"))
      (node (ref "U2") (pin "1") (pinfunction "STAT_1") (pintype "output"))
    )
    (net (code "57") (name "unconnected-(CN1-PadD+)") (class "Default")
      (node (ref "CN1") (pin "D+") (pinfunction "D+_D+") (pintype "bidirectional"))
    )
    (net (code "58") (name "unconnected-(CN1-PadD-)") (class "Default")
      (node (ref "CN1") (pin "D-") (pinfunction "D-_D-") (pintype "bidirectional"))
    )
    (net (code "59") (name "unconnected-(CN1-PadID)") (class "Default")
      (node (ref "CN1") (pin "ID") (pinfunction "ID_ID") (pintype "bidirectional"))
    )
    (net (code "60") (name "unconnected-(CN4-Pad2)") (class "Default")
      (node (ref "CN4") (pin "2") (pinfunction "2_2") (pintype "passive"))
    )
    (net (code "61") (name "unconnected-(L16-DOUT-Pad2-DOUT)") (class "Default")
      (node (ref "L16") (pin "2-DOUT") (pinfunction "DOUT_2-DOUT") (pintype "output"))
    )
  )
)
